# Arduino.net
KiCad netlist of a schematic drawn in Altium Designer
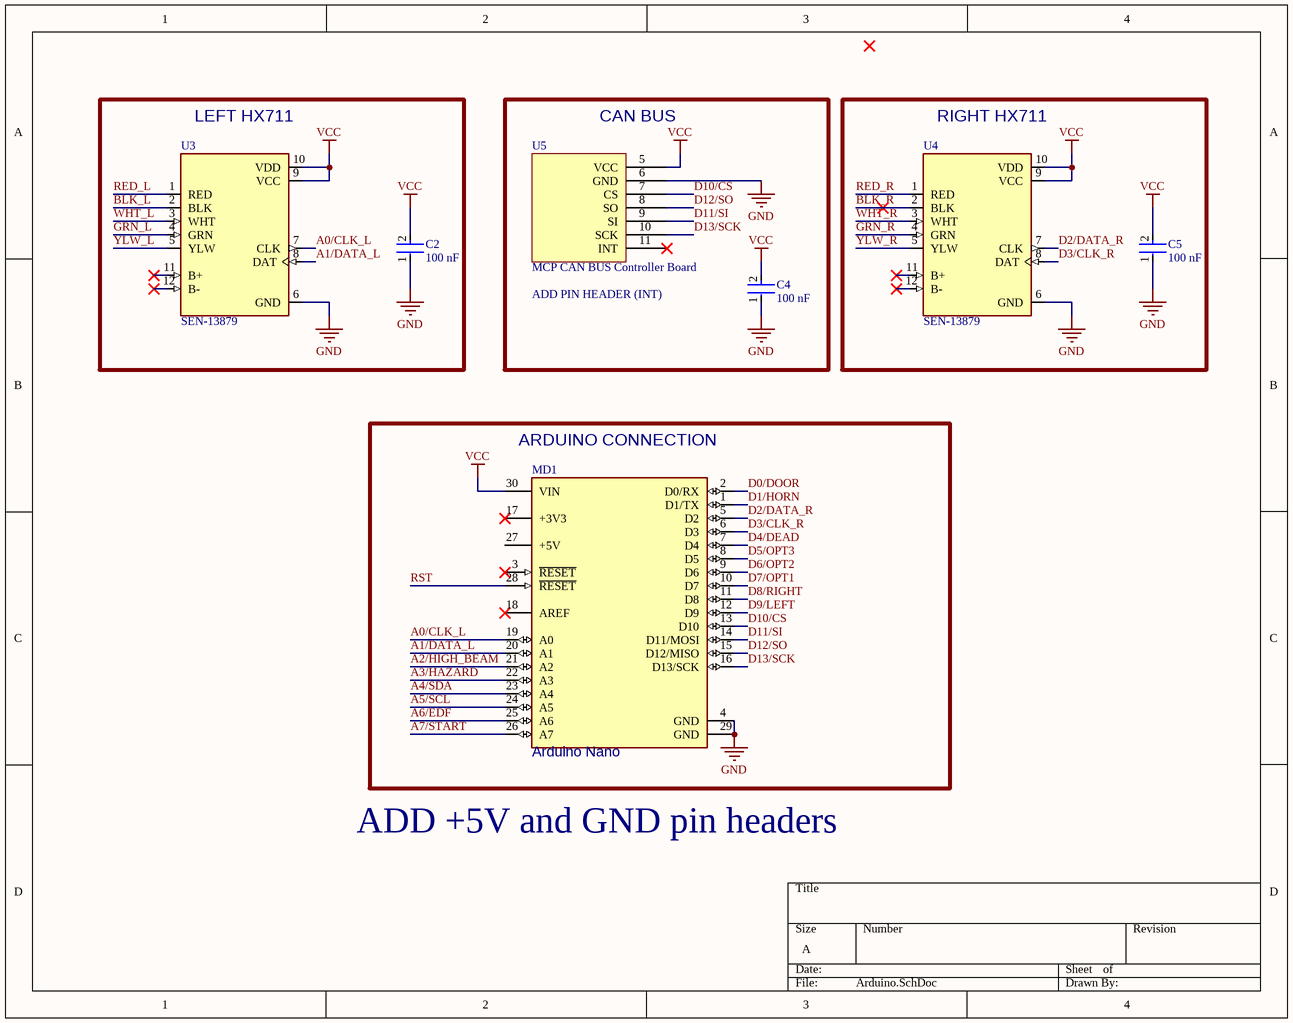
[diagram p0: Arduino.SchDoc]

(export (version "E")
  (design (tool "Eeschema 10.0.6"))
  (components
    (comp (ref "C2")
      (value "100 nF")
      (footprint "FP-562R5GAS10-MFG")
      (description "CAP CER 10000PF 1KV Z5U RADIAL")
      (fields (field (name "TOLERANCE") "20%") (field (name "VOLTAGE") "1kV"))
      (libsource (lib "Altium Content Vault") (part "6d4d395cd7362dd47ce0157d173177e"))
    )
    (comp (ref "C4")
      (value "100 nF")
      (footprint "FP-562R5GAS10-MFG")
      (description "CAP CER 10000PF 1KV Z5U RADIAL")
      (fields (field (name "TOLERANCE") "20%") (field (name "VOLTAGE") "1kV"))
      (libsource (lib "Altium Content Vault") (part "6d4d395cd7362dd47ce0157d173177e"))
    )
    (comp (ref "C5")
      (value "100 nF")
      (footprint "FP-562R5GAS10-MFG")
      (description "CAP CER 10000PF 1KV Z5U RADIAL")
      (fields (field (name "TOLERANCE") "20%") (field (name "VOLTAGE") "1kV"))
      (libsource (lib "Altium Content Vault") (part "6d4d395cd7362dd47ce0157d173177e"))
    )
    (comp (ref "MD1")
      (value "Arduino Nano")
      (footprint "FP-A000005-MFG")
      (description "ARDUINO NANO ATMEGA328 EVAL BRD")
      (libsource (lib "Altium Content Vault") (part "d190c066e99afd1c6882cf92e11b2cc"))
    )
    (comp (ref "U3")
      (value "SEN-13879")
      (footprint "SPARKFUN_SEN-13879")
      (description "Load Cell Amp Hx711")
      (libsource (lib "SEN-13879") (part "SEN-13879"))
    )
    (comp (ref "U4")
      (value "SEN-13879")
      (footprint "SPARKFUN_SEN-13879")
      (description "Load Cell Amp Hx711")
      (libsource (lib "SEN-13879") (part "SEN-13879"))
    )
    (comp (ref "U5")
      (value "MCP CAN BUS Controller Board")
      (footprint "MCP2515")
      (libsource (lib "MCP2515_Module") (part "MCP2515 Module"))
    )
  )
  (nets
    (net (code "1") (name "/A0{slash}CLK_L") (class "Default")
      (node (ref "MD1") (pin "19") (pinfunction "A0_19") (pintype "bidirectional"))
      (node (ref "U3") (pin "7") (pinfunction "CLK_7") (pintype "output"))
    )
    (net (code "2") (name "/A1{slash}DATA_L") (class "Default")
      (node (ref "MD1") (pin "20") (pinfunction "A1_20") (pintype "bidirectional"))
      (node (ref "U3") (pin "8") (pinfunction "DAT_8") (pintype "input"))
    )
    (net (code "3") (name "/A2{slash}HIGH_BEAM") (class "Default")
      (node (ref "MD1") (pin "21") (pinfunction "A2_21") (pintype "bidirectional"))
    )
    (net (code "4") (name "/A3{slash}HAZARD") (class "Default")
      (node (ref "MD1") (pin "22") (pinfunction "A3_22") (pintype "bidirectional"))
    )
    (net (code "5") (name "/A4{slash}SDA") (class "Default")
      (node (ref "MD1") (pin "23") (pinfunction "A4_23") (pintype "bidirectional"))
    )
    (net (code "6") (name "/A5{slash}SCL") (class "Default")
      (node (ref "MD1") (pin "24") (pinfunction "A5_24") (pintype "bidirectional"))
    )
    (net (code "7") (name "/A6{slash}EDF") (class "Default")
      (node (ref "MD1") (pin "25") (pinfunction "A6_25") (pintype "bidirectional"))
    )
    (net (code "8") (name "/A7{slash}START") (class "Default")
      (node (ref "MD1") (pin "26") (pinfunction "A7_26") (pintype "bidirectional"))
    )
    (net (code "9") (name "/BLK_L") (class "Default")
      (node (ref "U3") (pin "2") (pinfunction "BLK_2") (pintype "bidirectional"))
    )
    (net (code "10") (name "/BLK_R") (class "Default")
      (node (ref "U4") (pin "2") (pinfunction "BLK_2") (pintype "bidirectional"))
    )
    (net (code "11") (name "/D0{slash}DOOR") (class "Default")
      (node (ref "MD1") (pin "2") (pinfunction "D0/RX_2") (pintype "bidirectional"))
    )
    (net (code "12") (name "/D1{slash}HORN") (class "Default")
      (node (ref "MD1") (pin "1") (pinfunction "D1/TX_1") (pintype "bidirectional"))
    )
    (net (code "13") (name "/D2{slash}DATA_R") (class "Default")
      (node (ref "MD1") (pin "5") (pinfunction "D2_5") (pintype "bidirectional"))
      (node (ref "U4") (pin "7") (pinfunction "CLK_7") (pintype "output"))
    )
    (net (code "14") (name "/D3{slash}CLK_R") (class "Default")
      (node (ref "MD1") (pin "6") (pinfunction "D3_6") (pintype "bidirectional"))
      (node (ref "U4") (pin "8") (pinfunction "DAT_8") (pintype "input"))
    )
    (net (code "15") (name "/D4{slash}DEAD") (class "Default")
      (node (ref "MD1") (pin "7") (pinfunction "D4_7") (pintype "bidirectional"))
    )
    (net (code "16") (name "/D5{slash}OPT3") (class "Default")
      (node (ref "MD1") (pin "8") (pinfunction "D5_8") (pintype "bidirectional"))
    )
    (net (code "17") (name "/D6{slash}OPT2") (class "Default")
      (node (ref "MD1") (pin "9") (pinfunction "D6_9") (pintype "bidirectional"))
    )
    (net (code "18") (name "/D7{slash}OPT1") (class "Default")
      (node (ref "MD1") (pin "10") (pinfunction "D7_10") (pintype "bidirectional"))
    )
    (net (code "19") (name "/D8{slash}RIGHT") (class "Default")
      (node (ref "MD1") (pin "11") (pinfunction "D8_11") (pintype "bidirectional"))
    )
    (net (code "20") (name "/D9{slash}LEFT") (class "Default")
      (node (ref "MD1") (pin "12") (pinfunction "D9_12") (pintype "bidirectional"))
    )
    (net (code "21") (name "/D10{slash}CS") (class "Default")
      (node (ref "MD1") (pin "13") (pinfunction "D10_13") (pintype "bidirectional"))
      (node (ref "U5") (pin "7") (pinfunction "CS_7") (pintype "passive"))
    )
    (net (code "22") (name "/D11{slash}SI") (class "Default")
      (node (ref "MD1") (pin "14") (pinfunction "D11/MOSI_14") (pintype "bidirectional"))
      (node (ref "U5") (pin "9") (pinfunction "SI_9") (pintype "passive"))
    )
    (net (code "23") (name "/D12{slash}SO") (class "Default")
      (node (ref "MD1") (pin "15") (pinfunction "D12/MISO_15") (pintype "bidirectional"))
      (node (ref "U5") (pin "8") (pinfunction "SO_8") (pintype "passive"))
    )
    (net (code "24") (name "/D13{slash}SCK") (class "Default")
      (node (ref "MD1") (pin "16") (pinfunction "D13/SCK_16") (pintype "bidirectional"))
      (node (ref "U5") (pin "10") (pinfunction "SCK_10") (pintype "passive"))
    )
    (net (code "25") (name "/GRN_L") (class "Default")
      (node (ref "U3") (pin "4") (pinfunction "GRN_4") (pintype "input"))
    )
    (net (code "26") (name "/GRN_R") (class "Default")
      (node (ref "U4") (pin "4") (pinfunction "GRN_4") (pintype "input"))
    )
    (net (code "27") (name "/RED_L") (class "Default")
      (node (ref "U3") (pin "1") (pinfunction "RED_1") (pintype "bidirectional"))
    )
    (net (code "28") (name "/RED_R") (class "Default")
      (node (ref "U4") (pin "1") (pinfunction "RED_1") (pintype "bidirectional"))
    )
    (net (code "29") (name "/RST") (class "Default")
      (node (ref "MD1") (pin "28") (pinfunction "~{RESET}_28") (pintype "input"))
    )
    (net (code "30") (name "/WHT_L") (class "Default")
      (node (ref "U3") (pin "3") (pinfunction "WHT_3") (pintype "input"))
    )
    (net (code "31") (name "/WHT_R") (class "Default")
      (node (ref "U4") (pin "3") (pinfunction "WHT_3") (pintype "input"))
    )
    (net (code "32") (name "/YLW_L") (class "Default")
      (node (ref "U3") (pin "5") (pinfunction "YLW_5") (pintype "bidirectional"))
    )
    (net (code "33") (name "/YLW_R") (class "Default")
      (node (ref "U4") (pin "5") (pinfunction "YLW_5") (pintype "bidirectional"))
    )
    (net (code "34") (name "GND") (class "Default")
      (node (ref "C2") (pin "1") (pinfunction "1_1") (pintype "passive"))
      (node (ref "C4") (pin "1") (pinfunction "1_1") (pintype "passive"))
      (node (ref "C5") (pin "1") (pinfunction "1_1") (pintype "passive"))
      (node (ref "MD1") (pin "29") (pinfunction "GND_29") (pintype "power_in"))
      (node (ref "MD1") (pin "4") (pinfunction "GND_4") (pintype "power_in"))
      (node (ref "U3") (pin "6") (pinfunction "GND_6") (pintype "power_in"))
      (node (ref "U4") (pin "6") (pinfunction "GND_6") (pintype "power_in"))
      (node (ref "U5") (pin "6") (pinfunction "GND_6") (pintype "passive"))
    )
    (net (code "35") (name "VCC") (class "Default")
      (node (ref "C2") (pin "2") (pinfunction "2_2") (pintype "passive"))
      (node (ref "C4") (pin "2") (pinfunction "2_2") (pintype "passive"))
      (node (ref "C5") (pin "2") (pinfunction "2_2") (pintype "passive"))
      (node (ref "MD1") (pin "30") (pinfunction "VIN_30") (pintype "power_in"))
      (node (ref "U3") (pin "10") (pinfunction "VDD_10") (pintype "power_in"))
      (node (ref "U3") (pin "9") (pinfunction "VCC_9") (pintype "power_in"))
      (node (ref "U4") (pin "10") (pinfunction "VDD_10") (pintype "power_in"))
      (node (ref "U4") (pin "9") (pinfunction "VCC_9") (pintype "power_in"))
      (node (ref "U5") (pin "5") (pinfunction "VCC_5") (pintype "passive"))
    )
    (net (code "36") (name "unconnected-(MD1-+3V3-Pad17)") (class "Default")
      (node (ref "MD1") (pin "17") (pinfunction "+3V3_17") (pintype "power_in+no_connect"))
    )
    (net (code "37") (name "unconnected-(MD1-+5V-Pad27)") (class "Default")
      (node (ref "MD1") (pin "27") (pinfunction "+5V_27") (pintype "power_in"))
    )
    (net (code "38") (name "unconnected-(MD1-AREF-Pad18)") (class "Default")
      (node (ref "MD1") (pin "18") (pinfunction "AREF_18") (pintype "passive+no_connect"))
    )
    (net (code "39") (name "unconnected-(MD1-~{RESET}-Pad3)") (class "Default")
      (node (ref "MD1") (pin "3") (pinfunction "~{RESET}_3") (pintype "input+no_connect"))
    )
    (net (code "40") (name "unconnected-(U3-B+-Pad11)") (class "Default")
      (node (ref "U3") (pin "11") (pinfunction "B+_11") (pintype "input+no_connect"))
    )
    (net (code "41") (name "unconnected-(U3-B--Pad12)") (class "Default")
      (node (ref "U3") (pin "12") (pinfunction "B-_12") (pintype "input+no_connect"))
    )
    (net (code "42") (name "unconnected-(U4-B+-Pad11)") (class "Default")
      (node (ref "U4") (pin "11") (pinfunction "B+_11") (pintype "input+no_connect"))
    )
    (net (code "43") (name "unconnected-(U4-B--Pad12)") (class "Default")
      (node (ref "U4") (pin "12") (pinfunction "B-_12") (pintype "input+no_connect"))
    )
    (net (code "44") (name "unconnected-(U5-INT-Pad11)") (class "Default")
      (node (ref "U5") (pin "11") (pinfunction "INT_11") (pintype "passive+no_connect"))
    )
  )
)
